# 1u_mixer.net
KiCad netlist of a schematic drawn in EAGLE
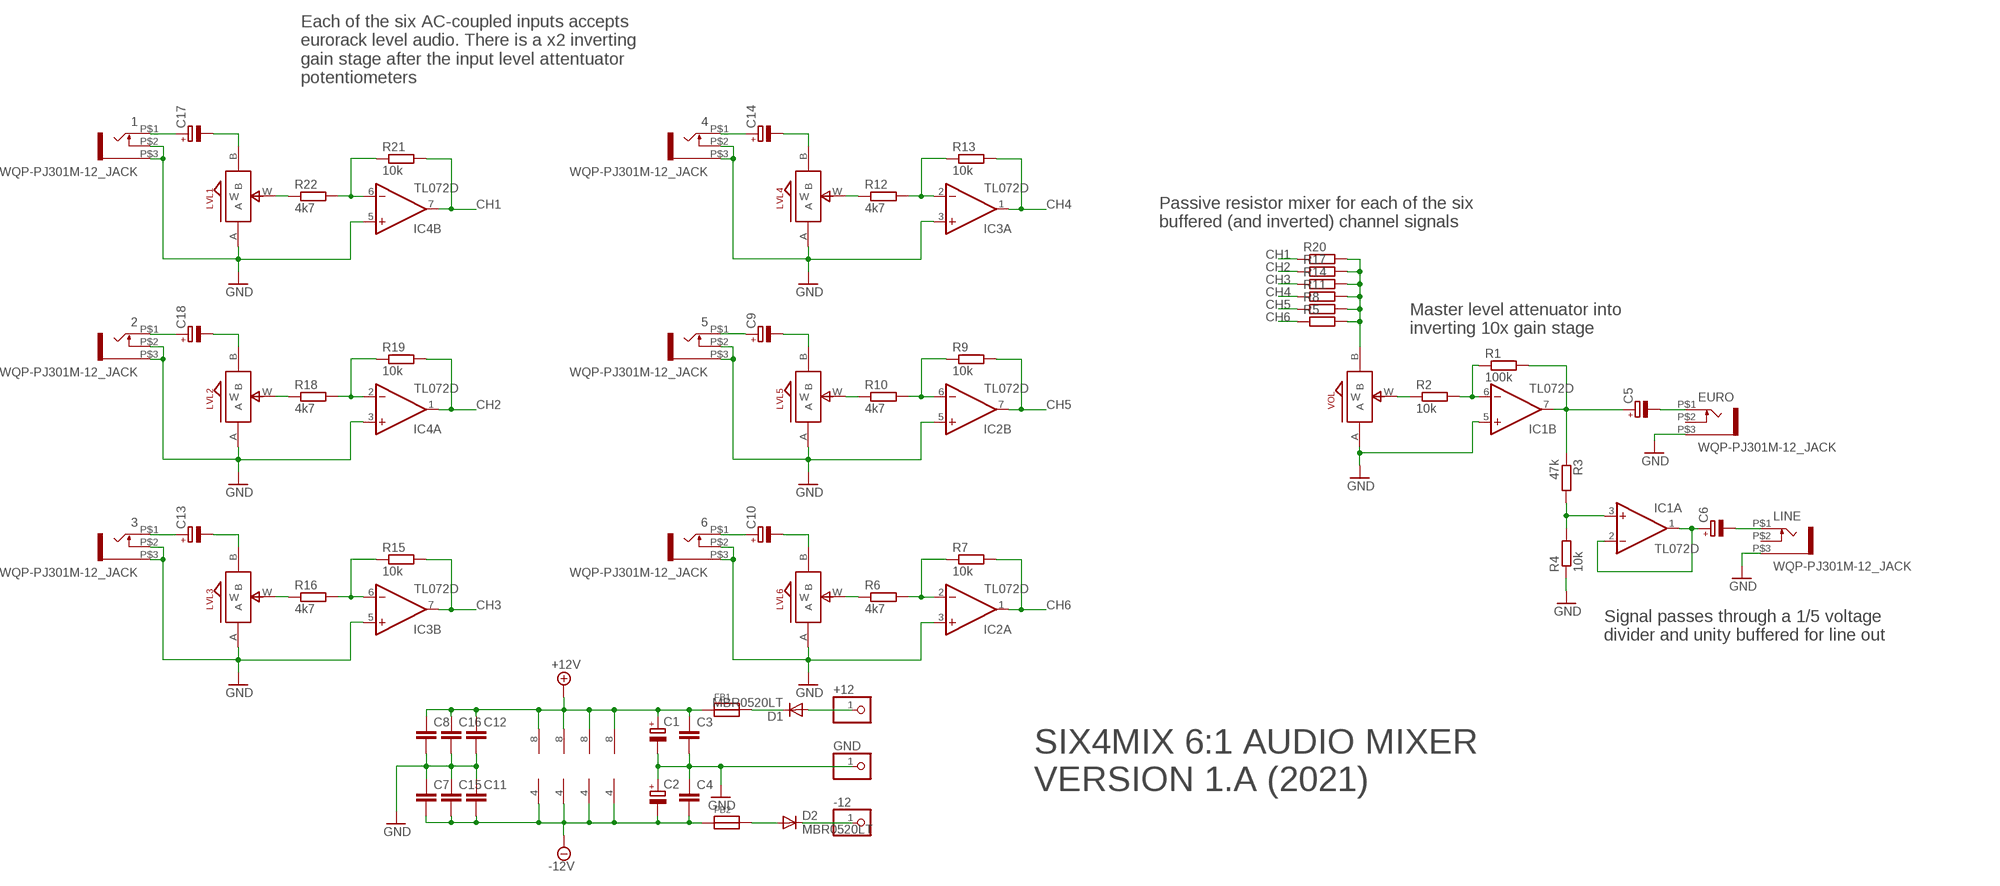
[diagram p0: schematic, sheet 1]

(export (version "E")
  (design (tool "Eeschema 10.0.6"))
  (components
    (comp (ref "+12")
      (value "PINHD-1X1")
      (footprint "eagle-import:1X01")
      (libsource (lib "eagle-import") (part "PINHD-1X1"))
    )
    (comp (ref "-12")
      (value "PINHD-1X1")
      (footprint "eagle-import:1X01")
      (libsource (lib "eagle-import") (part "PINHD-1X1"))
    )
    (comp (ref "1")
      (value "WQP-PJ301M-12_JACK")
      (footprint "eagle-import:WQP-PJ301M-12_JACK")
      (libsource (lib "eagle-import") (part "WQP-PJ301M-12_JACK"))
    )
    (comp (ref "2")
      (value "WQP-PJ301M-12_JACK")
      (footprint "eagle-import:WQP-PJ301M-12_JACK")
      (libsource (lib "eagle-import") (part "WQP-PJ301M-12_JACK"))
    )
    (comp (ref "3")
      (value "WQP-PJ301M-12_JACK")
      (footprint "eagle-import:WQP-PJ301M-12_JACK")
      (libsource (lib "eagle-import") (part "WQP-PJ301M-12_JACK"))
    )
    (comp (ref "4")
      (value "WQP-PJ301M-12_JACK")
      (footprint "eagle-import:WQP-PJ301M-12_JACK")
      (libsource (lib "eagle-import") (part "WQP-PJ301M-12_JACK"))
    )
    (comp (ref "5")
      (value "WQP-PJ301M-12_JACK")
      (footprint "eagle-import:WQP-PJ301M-12_JACK")
      (libsource (lib "eagle-import") (part "WQP-PJ301M-12_JACK"))
    )
    (comp (ref "6")
      (value "WQP-PJ301M-12_JACK")
      (footprint "eagle-import:WQP-PJ301M-12_JACK")
      (libsource (lib "eagle-import") (part "WQP-PJ301M-12_JACK"))
    )
    (comp (ref "C1")
      (value "CPOL-EUE2-4")
      (footprint "eagle-import:E2-4")
      (libsource (lib "eagle-import") (part "CPOL-EUE2-4"))
    )
    (comp (ref "C2")
      (value "CPOL-EUE2-4")
      (footprint "eagle-import:E2-4")
      (libsource (lib "eagle-import") (part "CPOL-EUE2-4"))
    )
    (comp (ref "C3")
      (value "C-EUC0805")
      (footprint "eagle-import:C0805")
      (libsource (lib "eagle-import") (part "C-EUC0805"))
    )
    (comp (ref "C4")
      (value "C-EUC0805")
      (footprint "eagle-import:C0805")
      (libsource (lib "eagle-import") (part "C-EUC0805"))
    )
    (comp (ref "C5")
      (value "CPOL-EUE2-4")
      (footprint "eagle-import:E2-4")
      (libsource (lib "eagle-import") (part "CPOL-EUE2-4"))
    )
    (comp (ref "C6")
      (value "CPOL-EUE2-4")
      (footprint "eagle-import:E2-4")
      (libsource (lib "eagle-import") (part "CPOL-EUE2-4"))
    )
    (comp (ref "C7")
      (value "C-EUC0805")
      (footprint "eagle-import:C0805")
      (libsource (lib "eagle-import") (part "C-EUC0805"))
    )
    (comp (ref "C8")
      (value "C-EUC0805")
      (footprint "eagle-import:C0805")
      (libsource (lib "eagle-import") (part "C-EUC0805"))
    )
    (comp (ref "C9")
      (value "CPOL-EUE2-4")
      (footprint "eagle-import:E2-4")
      (libsource (lib "eagle-import") (part "CPOL-EUE2-4"))
    )
    (comp (ref "C10")
      (value "CPOL-EUE2-4")
      (footprint "eagle-import:E2-4")
      (libsource (lib "eagle-import") (part "CPOL-EUE2-4"))
    )
    (comp (ref "C11")
      (value "C-EUC0805")
      (footprint "eagle-import:C0805")
      (libsource (lib "eagle-import") (part "C-EUC0805"))
    )
    (comp (ref "C12")
      (value "C-EUC0805")
      (footprint "eagle-import:C0805")
      (libsource (lib "eagle-import") (part "C-EUC0805"))
    )
    (comp (ref "C13")
      (value "CPOL-EUE2-4")
      (footprint "eagle-import:E2-4")
      (libsource (lib "eagle-import") (part "CPOL-EUE2-4"))
    )
    (comp (ref "C14")
      (value "CPOL-EUE2-4")
      (footprint "eagle-import:E2-4")
      (libsource (lib "eagle-import") (part "CPOL-EUE2-4"))
    )
    (comp (ref "C15")
      (value "C-EUC0805")
      (footprint "eagle-import:C0805")
      (libsource (lib "eagle-import") (part "C-EUC0805"))
    )
    (comp (ref "C16")
      (value "C-EUC0805")
      (footprint "eagle-import:C0805")
      (libsource (lib "eagle-import") (part "C-EUC0805"))
    )
    (comp (ref "C17")
      (value "CPOL-EUE2-4")
      (footprint "eagle-import:E2-4")
      (libsource (lib "eagle-import") (part "CPOL-EUE2-4"))
    )
    (comp (ref "C18")
      (value "CPOL-EUE2-4")
      (footprint "eagle-import:E2-4")
      (libsource (lib "eagle-import") (part "CPOL-EUE2-4"))
    )
    (comp (ref "D1")
      (value "MBR0520LT")
      (footprint "eagle-import:SOD123")
      (libsource (lib "eagle-import") (part "MBR0520LT"))
    )
    (comp (ref "D2")
      (value "MBR0520LT")
      (footprint "eagle-import:SOD123")
      (libsource (lib "eagle-import") (part "MBR0520LT"))
    )
    (comp (ref "EURO")
      (value "WQP-PJ301M-12_JACK")
      (footprint "eagle-import:WQP-PJ301M-12_JACK")
      (libsource (lib "eagle-import") (part "WQP-PJ301M-12_JACK"))
    )
    (comp (ref "FB1")
      (value "FERRITE")
      (footprint "eagle-import:0603")
      (libsource (lib "eagle-import") (part "FERRITE"))
    )
    (comp (ref "FB2")
      (value "FERRITE")
      (footprint "eagle-import:0603")
      (libsource (lib "eagle-import") (part "FERRITE"))
    )
    (comp (ref "GND")
      (value "PINHD-1X1")
      (footprint "eagle-import:1X01")
      (libsource (lib "eagle-import") (part "PINHD-1X1"))
    )
    (comp (ref "IC1")
      (value "TL072D")
      (footprint "eagle-import:SO08")
      (libsource (lib "eagle-import") (part "TL072D"))
    )
    (comp (ref "IC2")
      (value "TL072D")
      (footprint "eagle-import:SO08")
      (libsource (lib "eagle-import") (part "TL072D"))
    )
    (comp (ref "IC3")
      (value "TL072D")
      (footprint "eagle-import:SO08")
      (libsource (lib "eagle-import") (part "TL072D"))
    )
    (comp (ref "IC4")
      (value "TL072D")
      (footprint "eagle-import:SO08")
      (libsource (lib "eagle-import") (part "TL072D"))
    )
    (comp (ref "LINE")
      (value "WQP-PJ301M-12_JACK")
      (footprint "eagle-import:WQP-PJ301M-12_JACK")
      (libsource (lib "eagle-import") (part "WQP-PJ301M-12_JACK"))
    )
    (comp (ref "LVL1")
      (value "ALPS_POT_SMALL")
      (footprint "eagle-import:SMALL_ALPS_POT")
      (libsource (lib "eagle-import") (part "ALPS_POT_SMALL"))
    )
    (comp (ref "LVL2")
      (value "ALPS_POT_SMALL")
      (footprint "eagle-import:SMALL_ALPS_POT")
      (libsource (lib "eagle-import") (part "ALPS_POT_SMALL"))
    )
    (comp (ref "LVL3")
      (value "ALPS_POT_SMALL")
      (footprint "eagle-import:SMALL_ALPS_POT")
      (libsource (lib "eagle-import") (part "ALPS_POT_SMALL"))
    )
    (comp (ref "LVL4")
      (value "ALPS_POT_SMALL")
      (footprint "eagle-import:SMALL_ALPS_POT")
      (libsource (lib "eagle-import") (part "ALPS_POT_SMALL"))
    )
    (comp (ref "LVL5")
      (value "ALPS_POT_SMALL")
      (footprint "eagle-import:SMALL_ALPS_POT")
      (libsource (lib "eagle-import") (part "ALPS_POT_SMALL"))
    )
    (comp (ref "LVL6")
      (value "ALPS_POT_SMALL")
      (footprint "eagle-import:SMALL_ALPS_POT")
      (libsource (lib "eagle-import") (part "ALPS_POT_SMALL"))
    )
    (comp (ref "R1")
      (value "100k")
      (footprint "eagle-import:R0805")
      (libsource (lib "eagle-import") (part "R-EU_R0805"))
    )
    (comp (ref "R2")
      (value "10k")
      (footprint "eagle-import:R0805")
      (libsource (lib "eagle-import") (part "R-EU_R0805"))
    )
    (comp (ref "R3")
      (value "47k")
      (footprint "eagle-import:R0805")
      (libsource (lib "eagle-import") (part "R-EU_R0805"))
    )
    (comp (ref "R4")
      (value "10k")
      (footprint "eagle-import:R0805")
      (libsource (lib "eagle-import") (part "R-EU_R0805"))
    )
    (comp (ref "R5")
      (value "R-EU_R0805")
      (footprint "eagle-import:R0805")
      (libsource (lib "eagle-import") (part "R-EU_R0805"))
    )
    (comp (ref "R6")
      (value "4k7")
      (footprint "eagle-import:R0805")
      (libsource (lib "eagle-import") (part "R-EU_R0805"))
    )
    (comp (ref "R7")
      (value "10k")
      (footprint "eagle-import:R0805")
      (libsource (lib "eagle-import") (part "R-EU_R0805"))
    )
    (comp (ref "R8")
      (value "R-EU_R0805")
      (footprint "eagle-import:R0805")
      (libsource (lib "eagle-import") (part "R-EU_R0805"))
    )
    (comp (ref "R9")
      (value "10k")
      (footprint "eagle-import:R0805")
      (libsource (lib "eagle-import") (part "R-EU_R0805"))
    )
    (comp (ref "R10")
      (value "4k7")
      (footprint "eagle-import:R0805")
      (libsource (lib "eagle-import") (part "R-EU_R0805"))
    )
    (comp (ref "R11")
      (value "R-EU_R0805")
      (footprint "eagle-import:R0805")
      (libsource (lib "eagle-import") (part "R-EU_R0805"))
    )
    (comp (ref "R12")
      (value "4k7")
      (footprint "eagle-import:R0805")
      (libsource (lib "eagle-import") (part "R-EU_R0805"))
    )
    (comp (ref "R13")
      (value "10k")
      (footprint "eagle-import:R0805")
      (libsource (lib "eagle-import") (part "R-EU_R0805"))
    )
    (comp (ref "R14")
      (value "R-EU_R0805")
      (footprint "eagle-import:R0805")
      (libsource (lib "eagle-import") (part "R-EU_R0805"))
    )
    (comp (ref "R15")
      (value "10k")
      (footprint "eagle-import:R0805")
      (libsource (lib "eagle-import") (part "R-EU_R0805"))
    )
    (comp (ref "R16")
      (value "4k7")
      (footprint "eagle-import:R0805")
      (libsource (lib "eagle-import") (part "R-EU_R0805"))
    )
    (comp (ref "R17")
      (value "R-EU_R0805")
      (footprint "eagle-import:R0805")
      (libsource (lib "eagle-import") (part "R-EU_R0805"))
    )
    (comp (ref "R18")
      (value "4k7")
      (footprint "eagle-import:R0805")
      (libsource (lib "eagle-import") (part "R-EU_R0805"))
    )
    (comp (ref "R19")
      (value "10k")
      (footprint "eagle-import:R0805")
      (libsource (lib "eagle-import") (part "R-EU_R0805"))
    )
    (comp (ref "R20")
      (value "R-EU_R0805")
      (footprint "eagle-import:R0805")
      (libsource (lib "eagle-import") (part "R-EU_R0805"))
    )
    (comp (ref "R21")
      (value "10k")
      (footprint "eagle-import:R0805")
      (libsource (lib "eagle-import") (part "R-EU_R0805"))
    )
    (comp (ref "R22")
      (value "4k7")
      (footprint "eagle-import:R0805")
      (libsource (lib "eagle-import") (part "R-EU_R0805"))
    )
    (comp (ref "VOL")
      (value "ALPS_POT_SMALL")
      (footprint "eagle-import:SMALL_ALPS_POT")
      (libsource (lib "eagle-import") (part "ALPS_POT_SMALL"))
    )
  )
  (nets
    (net (code "1") (name "+12V") (class "Default")
      (node (ref "C1") (pin "+") (pinfunction "+_+") (pintype "passive"))
      (node (ref "C12") (pin "1") (pinfunction "1_1") (pintype "passive"))
      (node (ref "C16") (pin "1") (pinfunction "1_1") (pintype "passive"))
      (node (ref "C3") (pin "1") (pinfunction "1_1") (pintype "passive"))
      (node (ref "C8") (pin "1") (pinfunction "1_1") (pintype "passive"))
      (node (ref "FB1") (pin "1") (pinfunction "P$1_1") (pintype "bidirectional"))
      (node (ref "IC1") (pin "8") (pinfunction "V+_8") (pintype "power_in"))
      (node (ref "IC2") (pin "8") (pinfunction "V+_8") (pintype "power_in"))
      (node (ref "IC3") (pin "8") (pinfunction "V+_8") (pintype "power_in"))
      (node (ref "IC4") (pin "8") (pinfunction "V+_8") (pintype "power_in"))
    )
    (net (code "2") (name "-12V") (class "Default")
      (node (ref "C11") (pin "2") (pinfunction "2_2") (pintype "passive"))
      (node (ref "C15") (pin "2") (pinfunction "2_2") (pintype "passive"))
      (node (ref "C2") (pin "-") (pinfunction "-_-") (pintype "passive"))
      (node (ref "C4") (pin "2") (pinfunction "2_2") (pintype "passive"))
      (node (ref "C7") (pin "2") (pinfunction "2_2") (pintype "passive"))
      (node (ref "FB2") (pin "1") (pinfunction "P$1_1") (pintype "bidirectional"))
      (node (ref "IC1") (pin "4") (pinfunction "V-_4") (pintype "power_in"))
      (node (ref "IC2") (pin "4") (pinfunction "V-_4") (pintype "power_in"))
      (node (ref "IC3") (pin "4") (pinfunction "V-_4") (pintype "power_in"))
      (node (ref "IC4") (pin "4") (pinfunction "V-_4") (pintype "power_in"))
    )
    (net (code "3") (name "/CH1") (class "Default")
      (node (ref "IC4") (pin "7") (pinfunction "OUT_7") (pintype "output"))
      (node (ref "R20") (pin "1") (pinfunction "1_1") (pintype "passive"))
      (node (ref "R21") (pin "2") (pinfunction "2_2") (pintype "passive"))
    )
    (net (code "4") (name "/CH2") (class "Default")
      (node (ref "IC4") (pin "1") (pinfunction "OUT_1") (pintype "output"))
      (node (ref "R17") (pin "1") (pinfunction "1_1") (pintype "passive"))
      (node (ref "R19") (pin "2") (pinfunction "2_2") (pintype "passive"))
    )
    (net (code "5") (name "/CH3") (class "Default")
      (node (ref "IC3") (pin "7") (pinfunction "OUT_7") (pintype "output"))
      (node (ref "R14") (pin "1") (pinfunction "1_1") (pintype "passive"))
      (node (ref "R15") (pin "2") (pinfunction "2_2") (pintype "passive"))
    )
    (net (code "6") (name "/CH4") (class "Default")
      (node (ref "IC3") (pin "1") (pinfunction "OUT_1") (pintype "output"))
      (node (ref "R11") (pin "1") (pinfunction "1_1") (pintype "passive"))
      (node (ref "R13") (pin "2") (pinfunction "2_2") (pintype "passive"))
    )
    (net (code "7") (name "/CH5") (class "Default")
      (node (ref "IC2") (pin "7") (pinfunction "OUT_7") (pintype "output"))
      (node (ref "R8") (pin "1") (pinfunction "1_1") (pintype "passive"))
      (node (ref "R9") (pin "2") (pinfunction "2_2") (pintype "passive"))
    )
    (net (code "8") (name "/CH6") (class "Default")
      (node (ref "IC2") (pin "1") (pinfunction "OUT_1") (pintype "output"))
      (node (ref "R5") (pin "1") (pinfunction "1_1") (pintype "passive"))
      (node (ref "R7") (pin "2") (pinfunction "2_2") (pintype "passive"))
    )
    (net (code "9") (name "GND") (class "Default")
      (node (ref "1") (pin "P$2") (pinfunction "3_P$2") (pintype "passive"))
      (node (ref "1") (pin "P$3") (pinfunction "1_P$3") (pintype "passive"))
      (node (ref "2") (pin "P$2") (pinfunction "3_P$2") (pintype "passive"))
      (node (ref "2") (pin "P$3") (pinfunction "1_P$3") (pintype "passive"))
      (node (ref "3") (pin "P$2") (pinfunction "3_P$2") (pintype "passive"))
      (node (ref "3") (pin "P$3") (pinfunction "1_P$3") (pintype "passive"))
      (node (ref "4") (pin "P$2") (pinfunction "3_P$2") (pintype "passive"))
      (node (ref "4") (pin "P$3") (pinfunction "1_P$3") (pintype "passive"))
      (node (ref "5") (pin "P$2") (pinfunction "3_P$2") (pintype "passive"))
      (node (ref "5") (pin "P$3") (pinfunction "1_P$3") (pintype "passive"))
      (node (ref "6") (pin "P$2") (pinfunction "3_P$2") (pintype "passive"))
      (node (ref "6") (pin "P$3") (pinfunction "1_P$3") (pintype "passive"))
      (node (ref "C1") (pin "-") (pinfunction "-_-") (pintype "passive"))
      (node (ref "C11") (pin "1") (pinfunction "1_1") (pintype "passive"))
      (node (ref "C12") (pin "2") (pinfunction "2_2") (pintype "passive"))
      (node (ref "C15") (pin "1") (pinfunction "1_1") (pintype "passive"))
      (node (ref "C16") (pin "2") (pinfunction "2_2") (pintype "passive"))
      (node (ref "C2") (pin "+") (pinfunction "+_+") (pintype "passive"))
      (node (ref "C3") (pin "2") (pinfunction "2_2") (pintype "passive"))
      (node (ref "C4") (pin "1") (pinfunction "1_1") (pintype "passive"))
      (node (ref "C7") (pin "1") (pinfunction "1_1") (pintype "passive"))
      (node (ref "C8") (pin "2") (pinfunction "2_2") (pintype "passive"))
      (node (ref "EURO") (pin "P$3") (pinfunction "1_P$3") (pintype "passive"))
      (node (ref "GND") (pin "1") (pinfunction "1_1") (pintype "passive"))
      (node (ref "IC1") (pin "5") (pinfunction "+IN_5") (pintype "input"))
      (node (ref "IC2") (pin "3") (pinfunction "+IN_3") (pintype "input"))
      (node (ref "IC2") (pin "5") (pinfunction "+IN_5") (pintype "input"))
      (node (ref "IC3") (pin "3") (pinfunction "+IN_3") (pintype "input"))
      (node (ref "IC3") (pin "5") (pinfunction "+IN_5") (pintype "input"))
      (node (ref "IC4") (pin "3") (pinfunction "+IN_3") (pintype "input"))
      (node (ref "IC4") (pin "5") (pinfunction "+IN_5") (pintype "input"))
      (node (ref "LINE") (pin "P$3") (pinfunction "1_P$3") (pintype "passive"))
      (node (ref "LVL1") (pin "A") (pinfunction "A_A") (pintype "bidirectional"))
      (node (ref "LVL2") (pin "A") (pinfunction "A_A") (pintype "bidirectional"))
      (node (ref "LVL3") (pin "A") (pinfunction "A_A") (pintype "bidirectional"))
      (node (ref "LVL4") (pin "A") (pinfunction "A_A") (pintype "bidirectional"))
      (node (ref "LVL5") (pin "A") (pinfunction "A_A") (pintype "bidirectional"))
      (node (ref "LVL6") (pin "A") (pinfunction "A_A") (pintype "bidirectional"))
      (node (ref "R4") (pin "1") (pinfunction "1_1") (pintype "passive"))
      (node (ref "VOL") (pin "A") (pinfunction "A_A") (pintype "bidirectional"))
    )
    (net (code "10") (name "Net-(+12-Pad1)") (class "Default")
      (node (ref "+12") (pin "1") (pinfunction "1_1") (pintype "passive"))
      (node (ref "D1") (pin "A") (pinfunction "A_A") (pintype "passive"))
    )
    (net (code "11") (name "Net-(-12-Pad1)") (class "Default")
      (node (ref "-12") (pin "1") (pinfunction "1_1") (pintype "passive"))
      (node (ref "D2") (pin "C") (pinfunction "C_C") (pintype "passive"))
    )
    (net (code "12") (name "Net-(1-2)") (class "Default")
      (node (ref "1") (pin "P$1") (pinfunction "2_P$1") (pintype "passive"))
      (node (ref "C17") (pin "+") (pinfunction "+_+") (pintype "passive"))
    )
    (net (code "13") (name "Net-(2-2)") (class "Default")
      (node (ref "2") (pin "P$1") (pinfunction "2_P$1") (pintype "passive"))
      (node (ref "C18") (pin "+") (pinfunction "+_+") (pintype "passive"))
    )
    (net (code "14") (name "Net-(3-2)") (class "Default")
      (node (ref "3") (pin "P$1") (pinfunction "2_P$1") (pintype "passive"))
      (node (ref "C13") (pin "+") (pinfunction "+_+") (pintype "passive"))
    )
    (net (code "15") (name "Net-(4-2)") (class "Default")
      (node (ref "4") (pin "P$1") (pinfunction "2_P$1") (pintype "passive"))
      (node (ref "C14") (pin "+") (pinfunction "+_+") (pintype "passive"))
    )
    (net (code "16") (name "Net-(5-2)") (class "Default")
      (node (ref "5") (pin "P$1") (pinfunction "2_P$1") (pintype "passive"))
      (node (ref "C9") (pin "+") (pinfunction "+_+") (pintype "passive"))
    )
    (net (code "17") (name "Net-(6-2)") (class "Default")
      (node (ref "6") (pin "P$1") (pinfunction "2_P$1") (pintype "passive"))
      (node (ref "C10") (pin "+") (pinfunction "+_+") (pintype "passive"))
    )
    (net (code "18") (name "Net-(C9-Pad-)") (class "Default")
      (node (ref "C9") (pin "-") (pinfunction "-_-") (pintype "passive"))
      (node (ref "LVL5") (pin "B") (pinfunction "B_B") (pintype "bidirectional"))
    )
    (net (code "19") (name "Net-(C10-Pad-)") (class "Default")
      (node (ref "C10") (pin "-") (pinfunction "-_-") (pintype "passive"))
      (node (ref "LVL6") (pin "B") (pinfunction "B_B") (pintype "bidirectional"))
    )
    (net (code "20") (name "Net-(C13-Pad-)") (class "Default")
      (node (ref "C13") (pin "-") (pinfunction "-_-") (pintype "passive"))
      (node (ref "LVL3") (pin "B") (pinfunction "B_B") (pintype "bidirectional"))
    )
    (net (code "21") (name "Net-(C14-Pad-)") (class "Default")
      (node (ref "C14") (pin "-") (pinfunction "-_-") (pintype "passive"))
      (node (ref "LVL4") (pin "B") (pinfunction "B_B") (pintype "bidirectional"))
    )
    (net (code "22") (name "Net-(C17-Pad-)") (class "Default")
      (node (ref "C17") (pin "-") (pinfunction "-_-") (pintype "passive"))
      (node (ref "LVL1") (pin "B") (pinfunction "B_B") (pintype "bidirectional"))
    )
    (net (code "23") (name "Net-(C18-Pad-)") (class "Default")
      (node (ref "C18") (pin "-") (pinfunction "-_-") (pintype "passive"))
      (node (ref "LVL2") (pin "B") (pinfunction "B_B") (pintype "bidirectional"))
    )
    (net (code "24") (name "Net-(EURO-2)") (class "Default")
      (node (ref "C5") (pin "-") (pinfunction "-_-") (pintype "passive"))
      (node (ref "EURO") (pin "P$1") (pinfunction "2_P$1") (pintype "passive"))
    )
    (net (code "25") (name "Net-(FB1-P$2)") (class "Default")
      (node (ref "D1") (pin "C") (pinfunction "C_C") (pintype "passive"))
      (node (ref "FB1") (pin "2") (pinfunction "P$2_2") (pintype "bidirectional"))
    )
    (net (code "26") (name "Net-(FB2-P$2)") (class "Default")
      (node (ref "D2") (pin "A") (pinfunction "A_A") (pintype "passive"))
      (node (ref "FB2") (pin "2") (pinfunction "P$2_2") (pintype "bidirectional"))
    )
    (net (code "27") (name "Net-(IC1A-+IN)") (class "Default")
      (node (ref "IC1") (pin "3") (pinfunction "+IN_3") (pintype "input"))
      (node (ref "R3") (pin "2") (pinfunction "2_2") (pintype "passive"))
      (node (ref "R4") (pin "2") (pinfunction "2_2") (pintype "passive"))
    )
    (net (code "28") (name "Net-(IC1A--IN)") (class "Default")
      (node (ref "C6") (pin "+") (pinfunction "+_+") (pintype "passive"))
      (node (ref "IC1") (pin "1") (pinfunction "OUT_1") (pintype "output"))
      (node (ref "IC1") (pin "2") (pinfunction "-IN_2") (pintype "input"))
    )
    (net (code "29") (name "Net-(IC1B--IN)") (class "Default")
      (node (ref "IC1") (pin "6") (pinfunction "-IN_6") (pintype "input"))
      (node (ref "R1") (pin "1") (pinfunction "1_1") (pintype "passive"))
      (node (ref "R2") (pin "2") (pinfunction "2_2") (pintype "passive"))
    )
    (net (code "30") (name "Net-(IC1B-OUT)") (class "Default")
      (node (ref "C5") (pin "+") (pinfunction "+_+") (pintype "passive"))
      (node (ref "IC1") (pin "7") (pinfunction "OUT_7") (pintype "output"))
      (node (ref "R1") (pin "2") (pinfunction "2_2") (pintype "passive"))
      (node (ref "R3") (pin "1") (pinfunction "1_1") (pintype "passive"))
    )
    (net (code "31") (name "Net-(IC2A--IN)") (class "Default")
      (node (ref "IC2") (pin "2") (pinfunction "-IN_2") (pintype "input"))
      (node (ref "R6") (pin "2") (pinfunction "2_2") (pintype "passive"))
      (node (ref "R7") (pin "1") (pinfunction "1_1") (pintype "passive"))
    )
    (net (code "32") (name "Net-(IC2B--IN)") (class "Default")
      (node (ref "IC2") (pin "6") (pinfunction "-IN_6") (pintype "input"))
      (node (ref "R10") (pin "2") (pinfunction "2_2") (pintype "passive"))
      (node (ref "R9") (pin "1") (pinfunction "1_1") (pintype "passive"))
    )
    (net (code "33") (name "Net-(IC3A--IN)") (class "Default")
      (node (ref "IC3") (pin "2") (pinfunction "-IN_2") (pintype "input"))
      (node (ref "R12") (pin "2") (pinfunction "2_2") (pintype "passive"))
      (node (ref "R13") (pin "1") (pinfunction "1_1") (pintype "passive"))
    )
    (net (code "34") (name "Net-(IC3B--IN)") (class "Default")
      (node (ref "IC3") (pin "6") (pinfunction "-IN_6") (pintype "input"))
      (node (ref "R15") (pin "1") (pinfunction "1_1") (pintype "passive"))
      (node (ref "R16") (pin "2") (pinfunction "2_2") (pintype "passive"))
    )
    (net (code "35") (name "Net-(IC4A--IN)") (class "Default")
      (node (ref "IC4") (pin "2") (pinfunction "-IN_2") (pintype "input"))
      (node (ref "R18") (pin "2") (pinfunction "2_2") (pintype "passive"))
      (node (ref "R19") (pin "1") (pinfunction "1_1") (pintype "passive"))
    )
    (net (code "36") (name "Net-(IC4B--IN)") (class "Default")
      (node (ref "IC4") (pin "6") (pinfunction "-IN_6") (pintype "input"))
      (node (ref "R21") (pin "1") (pinfunction "1_1") (pintype "passive"))
      (node (ref "R22") (pin "2") (pinfunction "2_2") (pintype "passive"))
    )
    (net (code "37") (name "Net-(LINE-2)") (class "Default")
      (node (ref "C6") (pin "-") (pinfunction "-_-") (pintype "passive"))
      (node (ref "LINE") (pin "P$1") (pinfunction "2_P$1") (pintype "passive"))
    )
    (net (code "38") (name "Net-(LVL1-PadW)") (class "Default")
      (node (ref "LVL1") (pin "W") (pinfunction "W_W") (pintype "bidirectional"))
      (node (ref "R22") (pin "1") (pinfunction "1_1") (pintype "passive"))
    )
    (net (code "39") (name "Net-(LVL2-PadW)") (class "Default")
      (node (ref "LVL2") (pin "W") (pinfunction "W_W") (pintype "bidirectional"))
      (node (ref "R18") (pin "1") (pinfunction "1_1") (pintype "passive"))
    )
    (net (code "40") (name "Net-(LVL3-PadW)") (class "Default")
      (node (ref "LVL3") (pin "W") (pinfunction "W_W") (pintype "bidirectional"))
      (node (ref "R16") (pin "1") (pinfunction "1_1") (pintype "passive"))
    )
    (net (code "41") (name "Net-(LVL4-PadW)") (class "Default")
      (node (ref "LVL4") (pin "W") (pinfunction "W_W") (pintype "bidirectional"))
      (node (ref "R12") (pin "1") (pinfunction "1_1") (pintype "passive"))
    )
    (net (code "42") (name "Net-(LVL5-PadW)") (class "Default")
      (node (ref "LVL5") (pin "W") (pinfunction "W_W") (pintype "bidirectional"))
      (node (ref "R10") (pin "1") (pinfunction "1_1") (pintype "passive"))
    )
    (net (code "43") (name "Net-(LVL6-PadW)") (class "Default")
      (node (ref "LVL6") (pin "W") (pinfunction "W_W") (pintype "bidirectional"))
      (node (ref "R6") (pin "1") (pinfunction "1_1") (pintype "passive"))
    )
    (net (code "44") (name "Net-(R2-Pad1)") (class "Default")
      (node (ref "R2") (pin "1") (pinfunction "1_1") (pintype "passive"))
      (node (ref "VOL") (pin "W") (pinfunction "W_W") (pintype "bidirectional"))
    )
    (net (code "45") (name "Net-(R11-Pad2)") (class "Default")
      (node (ref "R11") (pin "2") (pinfunction "2_2") (pintype "passive"))
      (node (ref "R14") (pin "2") (pinfunction "2_2") (pintype "passive"))
      (node (ref "R17") (pin "2") (pinfunction "2_2") (pintype "passive"))
      (node (ref "R20") (pin "2") (pinfunction "2_2") (pintype "passive"))
      (node (ref "R5") (pin "2") (pinfunction "2_2") (pintype "passive"))
      (node (ref "R8") (pin "2") (pinfunction "2_2") (pintype "passive"))
      (node (ref "VOL") (pin "B") (pinfunction "B_B") (pintype "bidirectional"))
    )
    (net (code "46") (name "unconnected-(EURO-3-PadP$2)") (class "Default")
      (node (ref "EURO") (pin "P$2") (pinfunction "3_P$2") (pintype "passive"))
    )
    (net (code "47") (name "unconnected-(LINE-3-PadP$2)") (class "Default")
      (node (ref "LINE") (pin "P$2") (pinfunction "3_P$2") (pintype "passive"))
    )
  )
)
